# MCU.net
KiCad netlist of a schematic drawn in Altium Designer
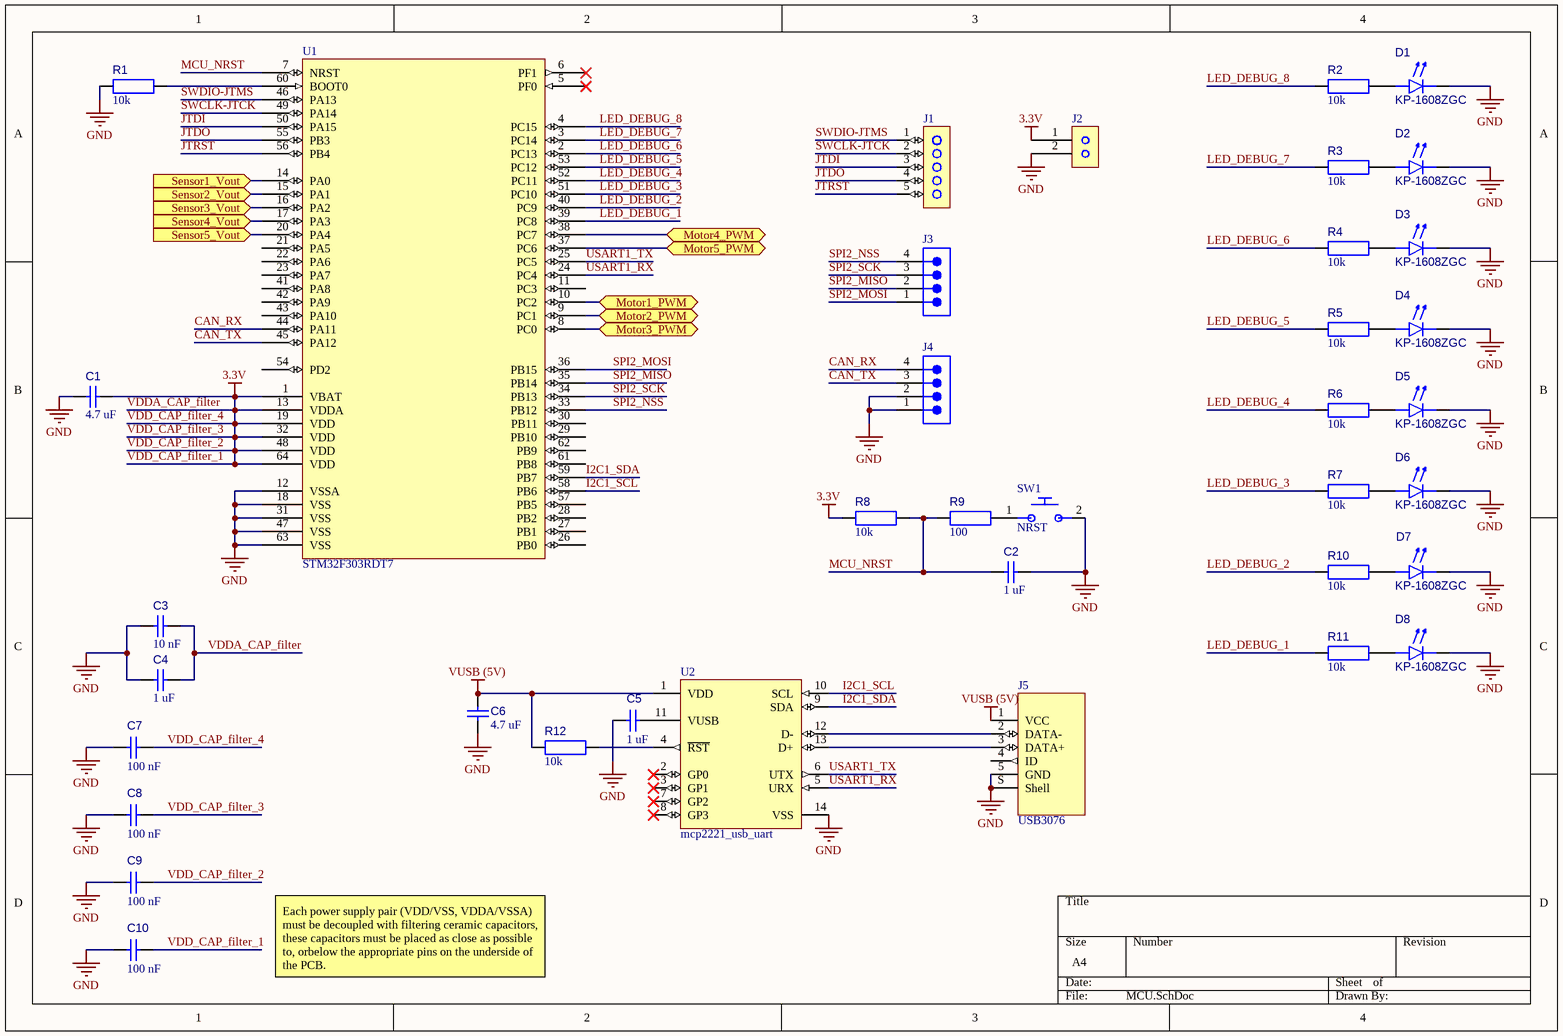
[diagram p0: MCU.SchDoc]

(export (version "E")
  (design (tool "Eeschema 10.0.6"))
  (components
    (comp (ref "C1")
      (value "Capacitor 0603 generic")
      (footprint "CAPC1608X08N")
      (description "Generic 0603 capacitor. No set voltage/capacitance rating.")
      (fields (field (name "CAPACITANCE") "4.7 uF"))
      (libsource (lib "Martin Kaur") (part "CAP-0603"))
    )
    (comp (ref "C2")
      (value "Capacitor 0603 generic")
      (footprint "CAPC1608X08N")
      (description "Generic 0603 capacitor. No set voltage/capacitance rating.")
      (fields (field (name "CAPACITANCE") "1 uF"))
      (libsource (lib "Martin Kaur") (part "CAP-0603"))
    )
    (comp (ref "C3")
      (value "Capacitor 0603 generic")
      (footprint "CAPC1608X08N")
      (description "Generic 0603 capacitor. No set voltage/capacitance rating.")
      (fields (field (name "CAPACITANCE") "10 nF"))
      (libsource (lib "Martin Kaur") (part "CAP-0603"))
    )
    (comp (ref "C4")
      (value "Capacitor 0603 generic")
      (footprint "CAPC1608X08N")
      (description "Generic 0603 capacitor. No set voltage/capacitance rating.")
      (fields (field (name "CAPACITANCE") "1 uF"))
      (libsource (lib "Martin Kaur") (part "CAP-0603"))
    )
    (comp (ref "C5")
      (value "Capacitor 0603 generic")
      (footprint "CAPC1608X08N")
      (description "Generic 0603 capacitor. No set voltage/capacitance rating.")
      (fields (field (name "CAPACITANCE") "1 uF"))
      (libsource (lib "Martin Kaur") (part "CAP-0603"))
    )
    (comp (ref "C6")
      (value "Capacitor 0603 generic")
      (footprint "CAPC1608X08N")
      (description "Generic 0603 capacitor. No set voltage/capacitance rating.")
      (fields (field (name "CAPACITANCE") "4.7 uF"))
      (libsource (lib "Martin Kaur") (part "CAP-0603"))
    )
    (comp (ref "C7")
      (value "Capacitor 0603 generic")
      (footprint "CAPC1608X08N")
      (description "Generic 0603 capacitor. No set voltage/capacitance rating.")
      (fields (field (name "CAPACITANCE") "100 nF"))
      (libsource (lib "Martin Kaur") (part "CAP-0603"))
    )
    (comp (ref "C8")
      (value "Capacitor 0603 generic")
      (footprint "CAPC1608X08N")
      (description "Generic 0603 capacitor. No set voltage/capacitance rating.")
      (fields (field (name "CAPACITANCE") "100 nF"))
      (libsource (lib "Martin Kaur") (part "CAP-0603"))
    )
    (comp (ref "C9")
      (value "Capacitor 0603 generic")
      (footprint "CAPC1608X08N")
      (description "Generic 0603 capacitor. No set voltage/capacitance rating.")
      (fields (field (name "CAPACITANCE") "100 nF"))
      (libsource (lib "Martin Kaur") (part "CAP-0603"))
    )
    (comp (ref "C10")
      (value "Capacitor 0603 generic")
      (footprint "CAPC1608X08N")
      (description "Generic 0603 capacitor. No set voltage/capacitance rating.")
      (fields (field (name "CAPACITANCE") "100 nF"))
      (libsource (lib "Martin Kaur") (part "CAP-0603"))
    )
    (comp (ref "D1")
      (value "KP-1608ZGC")
      (footprint "DIOM1608X11N")
      (description "Single Color LED, Green, Water Clear, 1.2mm")
      (libsource (lib "Martin Kaur") (part "KP-1608ZGC"))
    )
    (comp (ref "D2")
      (value "KP-1608ZGC")
      (footprint "DIOM1608X11N")
      (description "Single Color LED, Green, Water Clear, 1.2mm")
      (libsource (lib "Martin Kaur") (part "KP-1608ZGC"))
    )
    (comp (ref "D3")
      (value "KP-1608ZGC")
      (footprint "DIOM1608X11N")
      (description "Single Color LED, Green, Water Clear, 1.2mm")
      (libsource (lib "Martin Kaur") (part "KP-1608ZGC"))
    )
    (comp (ref "D4")
      (value "KP-1608ZGC")
      (footprint "DIOM1608X11N")
      (description "Single Color LED, Green, Water Clear, 1.2mm")
      (libsource (lib "Martin Kaur") (part "KP-1608ZGC"))
    )
    (comp (ref "D5")
      (value "KP-1608ZGC")
      (footprint "DIOM1608X11N")
      (description "Single Color LED, Green, Water Clear, 1.2mm")
      (libsource (lib "Martin Kaur") (part "KP-1608ZGC"))
    )
    (comp (ref "D6")
      (value "KP-1608ZGC")
      (footprint "DIOM1608X11N")
      (description "Single Color LED, Green, Water Clear, 1.2mm")
      (libsource (lib "Martin Kaur") (part "KP-1608ZGC"))
    )
    (comp (ref "D7")
      (value "KP-1608ZGC")
      (footprint "DIOM1608X11N")
      (description "Single Color LED, Green, Water Clear, 1.2mm")
      (libsource (lib "Martin Kaur") (part "KP-1608ZGC"))
    )
    (comp (ref "D8")
      (value "KP-1608ZGC")
      (footprint "DIOM1608X11N")
      (description "Single Color LED, Green, Water Clear, 1.2mm")
      (libsource (lib "Martin Kaur") (part "KP-1608ZGC"))
    )
    (comp (ref "J1")
      (value "Header-2.54-ZL201-05G")
      (footprint "Header-2.54-ZL201-05G-Footprint-1")
      (description "Male header, pitch 2.54 mm, 1x5 pins")
      (libsource (lib "Martin Kaur") (part "Header-2.54-ZL201-05G"))
    )
    (comp (ref "J2")
      (value "2_pin_f_2_54")
      (footprint "2_pin_f_2_54-Footprint-1")
      (description "2 pin female header, 2.54 mm pitch.")
      (libsource (lib "Martin Kaur") (part "2_pin_header"))
    )
    (comp (ref "J3")
      (value "MTLW-104-07-F-S-125")
      (footprint "SMTC-MTLW-104-07-X-S-125")
      (fields (field (name "MANUFACTURER") "Samtec"))
      (libsource (lib "Altium Content Vault") (part "SMTC-MTLW-104-07-X-S-125"))
    )
    (comp (ref "J4")
      (value "MTLW-104-07-F-S-125")
      (footprint "SMTC-MTLW-104-07-X-S-125")
      (fields (field (name "MANUFACTURER") "Samtec"))
      (libsource (lib "Altium Content Vault") (part "SMTC-MTLW-104-07-X-S-125"))
    )
    (comp (ref "J5")
      (value "USB3076")
      (footprint "USB3076-XX-X_revC")
      (libsource (lib "Martin Kaur") (part "USB3076-XX-X_revC"))
    )
    (comp (ref "R1")
      (value "Resistor 0603 generic")
      (footprint "RESC1608X04N")
      (description "Generic 0603 resistor, no fixed value.")
      (fields (field (name "RESISTANCE") "10k"))
      (libsource (lib "Martin Kaur") (part "RES0603"))
    )
    (comp (ref "R2")
      (value "Resistor 0603 generic")
      (footprint "RESC1608X04N")
      (description "Generic 0603 resistor, no fixed value.")
      (fields (field (name "RESISTANCE") "10k"))
      (libsource (lib "Martin Kaur") (part "RES0603"))
    )
    (comp (ref "R3")
      (value "Resistor 0603 generic")
      (footprint "RESC1608X04N")
      (description "Generic 0603 resistor, no fixed value.")
      (fields (field (name "RESISTANCE") "10k"))
      (libsource (lib "Martin Kaur") (part "RES0603"))
    )
    (comp (ref "R4")
      (value "Resistor 0603 generic")
      (footprint "RESC1608X04N")
      (description "Generic 0603 resistor, no fixed value.")
      (fields (field (name "RESISTANCE") "10k"))
      (libsource (lib "Martin Kaur") (part "RES0603"))
    )
    (comp (ref "R5")
      (value "Resistor 0603 generic")
      (footprint "RESC1608X04N")
      (description "Generic 0603 resistor, no fixed value.")
      (fields (field (name "RESISTANCE") "10k"))
      (libsource (lib "Martin Kaur") (part "RES0603"))
    )
    (comp (ref "R6")
      (value "Resistor 0603 generic")
      (footprint "RESC1608X04N")
      (description "Generic 0603 resistor, no fixed value.")
      (fields (field (name "RESISTANCE") "10k"))
      (libsource (lib "Martin Kaur") (part "RES0603"))
    )
    (comp (ref "R7")
      (value "Resistor 0603 generic")
      (footprint "RESC1608X04N")
      (description "Generic 0603 resistor, no fixed value.")
      (fields (field (name "RESISTANCE") "10k"))
      (libsource (lib "Martin Kaur") (part "RES0603"))
    )
    (comp (ref "R8")
      (value "Resistor 0603 generic")
      (footprint "RESC1608X04N")
      (description "Generic 0603 resistor, no fixed value.")
      (fields (field (name "RESISTANCE") "10k"))
      (libsource (lib "Martin Kaur") (part "RES0603"))
    )
    (comp (ref "R9")
      (value "Resistor 0603 generic")
      (footprint "RESC1608X04N")
      (description "Generic 0603 resistor, no fixed value.")
      (fields (field (name "RESISTANCE") "100"))
      (libsource (lib "Martin Kaur") (part "RES0603"))
    )
    (comp (ref "R10")
      (value "Resistor 0603 generic")
      (footprint "RESC1608X04N")
      (description "Generic 0603 resistor, no fixed value.")
      (fields (field (name "RESISTANCE") "10k"))
      (libsource (lib "Martin Kaur") (part "RES0603"))
    )
    (comp (ref "R11")
      (value "Resistor 0603 generic")
      (footprint "RESC1608X04N")
      (description "Generic 0603 resistor, no fixed value.")
      (fields (field (name "RESISTANCE") "10k"))
      (libsource (lib "Martin Kaur") (part "RES0603"))
    )
    (comp (ref "R12")
      (value "Resistor 0603 generic")
      (footprint "RESC1608X04N")
      (description "Generic 0603 resistor, no fixed value.")
      (fields (field (name "RESISTANCE") "10k"))
      (libsource (lib "Martin Kaur") (part "RES0603"))
    )
    (comp (ref "SW1")
      (value "NRST")
      (footprint "Button 6mm tht-Footprint-1")
      (description "Button 6mm tht")
      (libsource (lib "Martin Kaur") (part "Button"))
    )
    (comp (ref "U1")
      (value "STM32F303RDT7")
      (footprint "LQFP50P1235X1235X165-64N")
      (description "ARM Microcontroller, 32-Bit, FLASH, CORTEX-M4F CPU, 72MHz, CMOS, LQFP64")
      (libsource (lib "Martin Kaur") (part "stm32f303rdt7"))
    )
    (comp (ref "U2")
      (value "mcp2221_usb_uart")
      (footprint "FP-C04-065-SL-IPC_B")
      (description "Usb uart converter.")
      (libsource (lib "Martin Kaur") (part "USB-UART"))
    )
  )
  (nets
    (net (code "1") (name "/CAN_RX") (class "Default")
      (node (ref "J4") (pin "4") (pinfunction "4_4") (pintype "passive"))
      (node (ref "U1") (pin "44") (pinfunction "PA11_44") (pintype "bidirectional"))
    )
    (net (code "2") (name "/CAN_TX") (class "Default")
      (node (ref "J4") (pin "3") (pinfunction "3_3") (pintype "passive"))
      (node (ref "U1") (pin "45") (pinfunction "PA12_45") (pintype "bidirectional"))
    )
    (net (code "3") (name "/I2C1_SCL") (class "Default")
      (node (ref "U1") (pin "58") (pinfunction "PB6_58") (pintype "bidirectional"))
      (node (ref "U2") (pin "10") (pinfunction "SCL_10") (pintype "input"))
    )
    (net (code "4") (name "/I2C1_SDA") (class "Default")
      (node (ref "U1") (pin "59") (pinfunction "PB7_59") (pintype "bidirectional"))
      (node (ref "U2") (pin "9") (pinfunction "SDA_9") (pintype "bidirectional"))
    )
    (net (code "5") (name "/JTDI") (class "Default")
      (node (ref "J1") (pin "3") (pinfunction "3_3") (pintype "bidirectional"))
      (node (ref "U1") (pin "50") (pinfunction "PA15_50") (pintype "bidirectional"))
    )
    (net (code "6") (name "/JTDO") (class "Default")
      (node (ref "J1") (pin "4") (pinfunction "4_4") (pintype "bidirectional"))
      (node (ref "U1") (pin "55") (pinfunction "PB3_55") (pintype "bidirectional"))
    )
    (net (code "7") (name "/JTRST") (class "Default")
      (node (ref "J1") (pin "5") (pinfunction "5_5") (pintype "bidirectional"))
      (node (ref "U1") (pin "56") (pinfunction "PB4_56") (pintype "bidirectional"))
    )
    (net (code "8") (name "/LED_DEBUG_1") (class "Default")
      (node (ref "R11") (pin "1") (pinfunction "1_1") (pintype "passive"))
      (node (ref "U1") (pin "39") (pinfunction "PC8_39") (pintype "bidirectional"))
    )
    (net (code "9") (name "/LED_DEBUG_2") (class "Default")
      (node (ref "R10") (pin "1") (pinfunction "1_1") (pintype "passive"))
      (node (ref "U1") (pin "40") (pinfunction "PC9_40") (pintype "bidirectional"))
    )
    (net (code "10") (name "/LED_DEBUG_3") (class "Default")
      (node (ref "R7") (pin "1") (pinfunction "1_1") (pintype "passive"))
      (node (ref "U1") (pin "51") (pinfunction "PC10_51") (pintype "bidirectional"))
    )
    (net (code "11") (name "/LED_DEBUG_4") (class "Default")
      (node (ref "R6") (pin "1") (pinfunction "1_1") (pintype "passive"))
      (node (ref "U1") (pin "52") (pinfunction "PC11_52") (pintype "bidirectional"))
    )
    (net (code "12") (name "/LED_DEBUG_5") (class "Default")
      (node (ref "R5") (pin "1") (pinfunction "1_1") (pintype "passive"))
      (node (ref "U1") (pin "53") (pinfunction "PC12_53") (pintype "bidirectional"))
    )
    (net (code "13") (name "/LED_DEBUG_6") (class "Default")
      (node (ref "R4") (pin "1") (pinfunction "1_1") (pintype "passive"))
      (node (ref "U1") (pin "2") (pinfunction "PC13_2") (pintype "bidirectional"))
    )
    (net (code "14") (name "/LED_DEBUG_7") (class "Default")
      (node (ref "R3") (pin "1") (pinfunction "1_1") (pintype "passive"))
      (node (ref "U1") (pin "3") (pinfunction "PC14_3") (pintype "bidirectional"))
    )
    (net (code "15") (name "/LED_DEBUG_8") (class "Default")
      (node (ref "R2") (pin "1") (pinfunction "1_1") (pintype "passive"))
      (node (ref "U1") (pin "4") (pinfunction "PC15_4") (pintype "bidirectional"))
    )
    (net (code "16") (name "/MCU_NRST") (class "Default")
      (node (ref "C2") (pin "2") (pinfunction "2_2") (pintype "passive"))
      (node (ref "R8") (pin "2") (pinfunction "2_2") (pintype "passive"))
      (node (ref "R9") (pin "1") (pinfunction "1_1") (pintype "passive"))
      (node (ref "U1") (pin "7") (pinfunction "NRST_7") (pintype "bidirectional"))
    )
    (net (code "17") (name "/Motor1_PWM") (class "Default")
      (node (ref "U1") (pin "10") (pinfunction "PC2_10") (pintype "bidirectional"))
    )
    (net (code "18") (name "/Motor2_PWM") (class "Default")
      (node (ref "U1") (pin "9") (pinfunction "PC1_9") (pintype "bidirectional"))
    )
    (net (code "19") (name "/Motor3_PWM") (class "Default")
      (node (ref "U1") (pin "8") (pinfunction "PC0_8") (pintype "bidirectional"))
    )
    (net (code "20") (name "/Motor4_PWM") (class "Default")
      (node (ref "U1") (pin "38") (pinfunction "PC7_38") (pintype "bidirectional"))
    )
    (net (code "21") (name "/Motor5_PWM") (class "Default")
      (node (ref "U1") (pin "37") (pinfunction "PC6_37") (pintype "bidirectional"))
    )
    (net (code "22") (name "/SPI2_MISO") (class "Default")
      (node (ref "J3") (pin "2") (pinfunction "2_2") (pintype "passive"))
      (node (ref "U1") (pin "35") (pinfunction "PB14_35") (pintype "bidirectional"))
    )
    (net (code "23") (name "/SPI2_MOSI") (class "Default")
      (node (ref "J3") (pin "1") (pinfunction "1_1") (pintype "passive"))
      (node (ref "U1") (pin "36") (pinfunction "PB15_36") (pintype "bidirectional"))
    )
    (net (code "24") (name "/SPI2_NSS") (class "Default")
      (node (ref "J3") (pin "4") (pinfunction "4_4") (pintype "passive"))
      (node (ref "U1") (pin "33") (pinfunction "PB12_33") (pintype "bidirectional"))
    )
    (net (code "25") (name "/SPI2_SCK") (class "Default")
      (node (ref "J3") (pin "3") (pinfunction "3_3") (pintype "passive"))
      (node (ref "U1") (pin "34") (pinfunction "PB13_34") (pintype "bidirectional"))
    )
    (net (code "26") (name "/SWCLK-JTCK") (class "Default")
      (node (ref "J1") (pin "2") (pinfunction "2_2") (pintype "bidirectional"))
      (node (ref "U1") (pin "49") (pinfunction "PA14_49") (pintype "bidirectional"))
    )
    (net (code "27") (name "/SWDIO-JTMS") (class "Default")
      (node (ref "J1") (pin "1") (pinfunction "1_1") (pintype "bidirectional"))
      (node (ref "U1") (pin "46") (pinfunction "PA13_46") (pintype "bidirectional"))
    )
    (net (code "28") (name "/Sensor1_Vout") (class "Default")
      (node (ref "U1") (pin "14") (pinfunction "PA0_14") (pintype "bidirectional"))
    )
    (net (code "29") (name "/Sensor2_Vout") (class "Default")
      (node (ref "U1") (pin "15") (pinfunction "PA1_15") (pintype "bidirectional"))
    )
    (net (code "30") (name "/Sensor3_Vout") (class "Default")
      (node (ref "U1") (pin "16") (pinfunction "PA2_16") (pintype "bidirectional"))
    )
    (net (code "31") (name "/Sensor4_Vout") (class "Default")
      (node (ref "U1") (pin "17") (pinfunction "PA3_17") (pintype "bidirectional"))
    )
    (net (code "32") (name "/Sensor5_Vout") (class "Default")
      (node (ref "U1") (pin "20") (pinfunction "PA4_20") (pintype "bidirectional"))
    )
    (net (code "33") (name "/USART1_RX") (class "Default")
      (node (ref "U1") (pin "24") (pinfunction "PC4_24") (pintype "bidirectional"))
      (node (ref "U2") (pin "5") (pinfunction "URX_5") (pintype "input"))
    )
    (net (code "34") (name "/USART1_TX") (class "Default")
      (node (ref "U1") (pin "25") (pinfunction "PC5_25") (pintype "bidirectional"))
      (node (ref "U2") (pin "6") (pinfunction "UTX_6") (pintype "output"))
    )
    (net (code "35") (name "3.3V") (class "Default")
      (node (ref "C1") (pin "1") (pinfunction "1_1") (pintype "passive"))
      (node (ref "C10") (pin "1") (pinfunction "1_1") (pintype "passive"))
      (node (ref "C3") (pin "1") (pinfunction "1_1") (pintype "passive"))
      (node (ref "C4") (pin "1") (pinfunction "1_1") (pintype "passive"))
      (node (ref "C7") (pin "1") (pinfunction "1_1") (pintype "passive"))
      (node (ref "C8") (pin "1") (pinfunction "1_1") (pintype "passive"))
      (node (ref "C9") (pin "1") (pinfunction "1_1") (pintype "passive"))
      (node (ref "J2") (pin "1") (pinfunction "VDD_1") (pintype "power_in"))
      (node (ref "R8") (pin "1") (pinfunction "1_1") (pintype "passive"))
      (node (ref "U1") (pin "1") (pinfunction "VBAT_1") (pintype "power_in"))
      (node (ref "U1") (pin "13") (pinfunction "VDDA_13") (pintype "power_in"))
      (node (ref "U1") (pin "19") (pinfunction "VDD_19") (pintype "power_in"))
      (node (ref "U1") (pin "32") (pinfunction "VDD_32") (pintype "power_in"))
      (node (ref "U1") (pin "48") (pinfunction "VDD_48") (pintype "power_in"))
      (node (ref "U1") (pin "64") (pinfunction "VDD_64") (pintype "power_in"))
    )
    (net (code "36") (name "GND") (class "Default")
      (node (ref "C1") (pin "2") (pinfunction "2_2") (pintype "passive"))
      (node (ref "C10") (pin "2") (pinfunction "2_2") (pintype "passive"))
      (node (ref "C2") (pin "1") (pinfunction "1_1") (pintype "passive"))
      (node (ref "C3") (pin "2") (pinfunction "2_2") (pintype "passive"))
      (node (ref "C4") (pin "2") (pinfunction "2_2") (pintype "passive"))
      (node (ref "C5") (pin "2") (pinfunction "2_2") (pintype "passive"))
      (node (ref "C6") (pin "2") (pinfunction "2_2") (pintype "passive"))
      (node (ref "C7") (pin "2") (pinfunction "2_2") (pintype "passive"))
      (node (ref "C8") (pin "2") (pinfunction "2_2") (pintype "passive"))
      (node (ref "C9") (pin "2") (pinfunction "2_2") (pintype "passive"))
      (node (ref "D1") (pin "1") (pinfunction "-_1") (pintype "passive"))
      (node (ref "D2") (pin "1") (pinfunction "-_1") (pintype "passive"))
      (node (ref "D3") (pin "1") (pinfunction "-_1") (pintype "passive"))
      (node (ref "D4") (pin "1") (pinfunction "-_1") (pintype "passive"))
      (node (ref "D5") (pin "1") (pinfunction "-_1") (pintype "passive"))
      (node (ref "D6") (pin "1") (pinfunction "-_1") (pintype "passive"))
      (node (ref "D7") (pin "1") (pinfunction "-_1") (pintype "passive"))
      (node (ref "D8") (pin "1") (pinfunction "-_1") (pintype "passive"))
      (node (ref "J2") (pin "2") (pinfunction "GND_2") (pintype "power_in"))
      (node (ref "J4") (pin "1") (pinfunction "1_1") (pintype "passive"))
      (node (ref "J4") (pin "2") (pinfunction "2_2") (pintype "passive"))
      (node (ref "J5") (pin "5") (pinfunction "GND_5") (pintype "power_in"))
      (node (ref "J5") (pin "S") (pinfunction "Shell_S") (pintype "power_in"))
      (node (ref "R1") (pin "1") (pinfunction "1_1") (pintype "passive"))
      (node (ref "SW1") (pin "2") (pinfunction "2_2") (pintype "passive"))
      (node (ref "U1") (pin "12") (pinfunction "VSSA_12") (pintype "power_in"))
      (node (ref "U1") (pin "18") (pinfunction "VSS_18") (pintype "power_in"))
      (node (ref "U1") (pin "31") (pinfunction "VSS_31") (pintype "power_in"))
      (node (ref "U1") (pin "47") (pinfunction "VSS_47") (pintype "power_in"))
      (node (ref "U1") (pin "63") (pinfunction "VSS_63") (pintype "power_in"))
      (node (ref "U2") (pin "14") (pinfunction "VSS_14") (pintype "power_in"))
    )
    (net (code "37") (name "Net-(D1-+)") (class "Default")
      (node (ref "D1") (pin "2") (pinfunction "+_2") (pintype "passive"))
      (node (ref "R2") (pin "2") (pinfunction "2_2") (pintype "passive"))
    )
    (net (code "38") (name "Net-(D2-+)") (class "Default")
      (node (ref "D2") (pin "2") (pinfunction "+_2") (pintype "passive"))
      (node (ref "R3") (pin "2") (pinfunction "2_2") (pintype "passive"))
    )
    (net (code "39") (name "Net-(D3-+)") (class "Default")
      (node (ref "D3") (pin "2") (pinfunction "+_2") (pintype "passive"))
      (node (ref "R4") (pin "2") (pinfunction "2_2") (pintype "passive"))
    )
    (net (code "40") (name "Net-(D4-+)") (class "Default")
      (node (ref "D4") (pin "2") (pinfunction "+_2") (pintype "passive"))
      (node (ref "R5") (pin "2") (pinfunction "2_2") (pintype "passive"))
    )
    (net (code "41") (name "Net-(D5-+)") (class "Default")
      (node (ref "D5") (pin "2") (pinfunction "+_2") (pintype "passive"))
      (node (ref "R6") (pin "2") (pinfunction "2_2") (pintype "passive"))
    )
    (net (code "42") (name "Net-(D6-+)") (class "Default")
      (node (ref "D6") (pin "2") (pinfunction "+_2") (pintype "passive"))
      (node (ref "R7") (pin "2") (pinfunction "2_2") (pintype "passive"))
    )
    (net (code "43") (name "Net-(D7-+)") (class "Default")
      (node (ref "D7") (pin "2") (pinfunction "+_2") (pintype "passive"))
      (node (ref "R10") (pin "2") (pinfunction "2_2") (pintype "passive"))
    )
    (net (code "44") (name "Net-(D8-+)") (class "Default")
      (node (ref "D8") (pin "2") (pinfunction "+_2") (pintype "passive"))
      (node (ref "R11") (pin "2") (pinfunction "2_2") (pintype "passive"))
    )
    (net (code "45") (name "Net-(J5-DATA+)") (class "Default")
      (node (ref "J5") (pin "3") (pinfunction "DATA+_3") (pintype "bidirectional"))
      (node (ref "U2") (pin "13") (pinfunction "D+_13") (pintype "bidirectional"))
    )
    (net (code "46") (name "Net-(J5-DATA-)") (class "Default")
      (node (ref "J5") (pin "2") (pinfunction "DATA-_2") (pintype "bidirectional"))
      (node (ref "U2") (pin "12") (pinfunction "D-_12") (pintype "bidirectional"))
    )
    (net (code "47") (name "Net-(R9-Pad2)") (class "Default")
      (node (ref "R9") (pin "2") (pinfunction "2_2") (pintype "passive"))
      (node (ref "SW1") (pin "1") (pinfunction "1_1") (pintype "passive"))
    )
    (net (code "48") (name "Net-(U1-BOOT0)") (class "Default")
      (node (ref "R1") (pin "2") (pinfunction "2_2") (pintype "passive"))
      (node (ref "U1") (pin "60") (pinfunction "BOOT0_60") (pintype "input"))
    )
    (net (code "49") (name "Net-(U2-VUSB)") (class "Default")
      (node (ref "C5") (pin "1") (pinfunction "1_1") (pintype "passive"))
      (node (ref "U2") (pin "11") (pinfunction "VUSB_11") (pintype "power_in"))
    )
    (net (code "50") (name "Net-(U2-~{RST})") (class "Default")
      (node (ref "R12") (pin "1") (pinfunction "1_1") (pintype "passive"))
      (node (ref "U2") (pin "4") (pinfunction "~{RST}_4") (pintype "output"))
    )
    (net (code "51") (name "VUSB (5V)") (class "Default")
      (node (ref "C6") (pin "1") (pinfunction "1_1") (pintype "passive"))
      (node (ref "J5") (pin "1") (pinfunction "VCC_1") (pintype "power_in"))
      (node (ref "R12") (pin "2") (pinfunction "2_2") (pintype "passive"))
      (node (ref "U2") (pin "1") (pinfunction "VDD_1") (pintype "power_in"))
    )
    (net (code "52") (name "unconnected-(J5-ID-Pad4)") (class "Default")
      (node (ref "J5") (pin "4") (pinfunction "ID_4") (pintype "output"))
    )
    (net (code "53") (name "unconnected-(U1-PA5-Pad21)") (class "Default")
      (node (ref "U1") (pin "21") (pinfunction "PA5_21") (pintype "bidirectional"))
    )
    (net (code "54") (name "unconnected-(U1-PA6-Pad22)") (class "Default")
      (node (ref "U1") (pin "22") (pinfunction "PA6_22") (pintype "bidirectional"))
    )
    (net (code "55") (name "unconnected-(U1-PA7-Pad23)") (class "Default")
      (node (ref "U1") (pin "23") (pinfunction "PA7_23") (pintype "bidirectional"))
    )
    (net (code "56") (name "unconnected-(U1-PA8-Pad41)") (class "Default")
      (node (ref "U1") (pin "41") (pinfunction "PA8_41") (pintype "bidirectional"))
    )
    (net (code "57") (name "unconnected-(U1-PA9-Pad42)") (class "Default")
      (node (ref "U1") (pin "42") (pinfunction "PA9_42") (pintype "bidirectional"))
    )
    (net (code "58") (name "unconnected-(U1-PA10-Pad43)") (class "Default")
      (node (ref "U1") (pin "43") (pinfunction "PA10_43") (pintype "bidirectional"))
    )
    (net (code "59") (name "unconnected-(U1-PB0-Pad26)") (class "Default")
      (node (ref "U1") (pin "26") (pinfunction "PB0_26") (pintype "bidirectional"))
    )
    (net (code "60") (name "unconnected-(U1-PB1-Pad27)") (class "Default")
      (node (ref "U1") (pin "27") (pinfunction "PB1_27") (pintype "bidirectional"))
    )
    (net (code "61") (name "unconnected-(U1-PB2-Pad28)") (class "Default")
      (node (ref "U1") (pin "28") (pinfunction "PB2_28") (pintype "bidirectional"))
    )
    (net (code "62") (name "unconnected-(U1-PB5-Pad57)") (class "Default")
      (node (ref "U1") (pin "57") (pinfunction "PB5_57") (pintype "bidirectional"))
    )
    (net (code "63") (name "unconnected-(U1-PB8-Pad61)") (class "Default")
      (node (ref "U1") (pin "61") (pinfunction "PB8_61") (pintype "bidirectional"))
    )
    (net (code "64") (name "unconnected-(U1-PB9-Pad62)") (class "Default")
      (node (ref "U1") (pin "62") (pinfunction "PB9_62") (pintype "bidirectional"))
    )
    (net (code "65") (name "unconnected-(U1-PB10-Pad29)") (class "Default")
      (node (ref "U1") (pin "29") (pinfunction "PB10_29") (pintype "bidirectional"))
    )
    (net (code "66") (name "unconnected-(U1-PB11-Pad30)") (class "Default")
      (node (ref "U1") (pin "30") (pinfunction "PB11_30") (pintype "bidirectional"))
    )
    (net (code "67") (name "unconnected-(U1-PC3-Pad11)") (class "Default")
      (node (ref "U1") (pin "11") (pinfunction "PC3_11") (pintype "bidirectional"))
    )
    (net (code "68") (name "unconnected-(U1-PD2-Pad54)") (class "Default")
      (node (ref "U1") (pin "54") (pinfunction "PD2_54") (pintype "bidirectional"))
    )
    (net (code "69") (name "unconnected-(U1-PF0-Pad5)") (class "Default")
      (node (ref "U1") (pin "5") (pinfunction "PF0_5") (pintype "input+no_connect"))
    )
    (net (code "70") (name "unconnected-(U1-PF1-Pad6)") (class "Default")
      (node (ref "U1") (pin "6") (pinfunction "PF1_6") (pintype "output+no_connect"))
    )
    (net (code "71") (name "unconnected-(U2-GP0-Pad2)") (class "Default")
      (node (ref "U2") (pin "2") (pinfunction "GP0_2") (pintype "bidirectional+no_connect"))
    )
    (net (code "72") (name "unconnected-(U2-GP1-Pad3)") (class "Default")
      (node (ref "U2") (pin "3") (pinfunction "GP1_3") (pintype "bidirectional+no_connect"))
    )
    (net (code "73") (name "unconnected-(U2-GP2-Pad7)") (class "Default")
      (node (ref "U2") (pin "7") (pinfunction "GP2_7") (pintype "bidirectional+no_connect"))
    )
    (net (code "74") (name "unconnected-(U2-GP3-Pad8)") (class "Default")
      (node (ref "U2") (pin "8") (pinfunction "GP3_8") (pintype "bidirectional+no_connect"))
    )
  )
)
